# Sheet1.net
KiCad netlist of a schematic drawn in Altium Designer
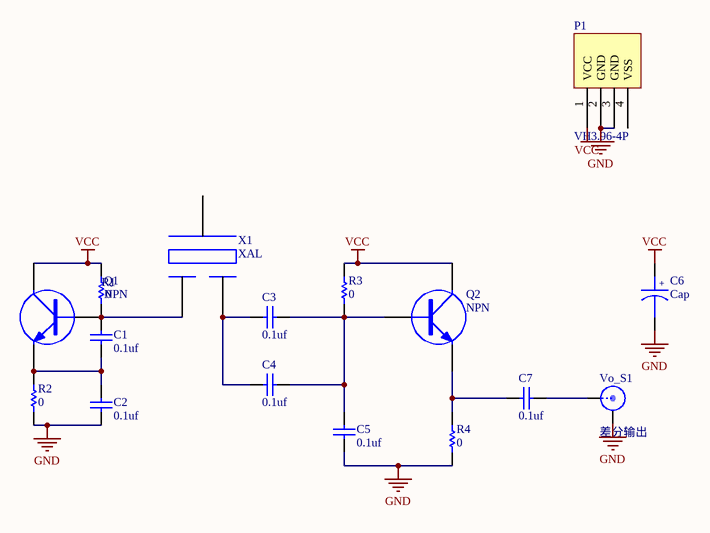
[diagram p0: Sheet1.SchDoc]

(export (version "E")
  (design (tool "Eeschema 10.0.6"))
  (components
    (comp (ref "C1") (value "0.1uf") (footprint "0805") (libsource (lib "Schlib1") (part "Cap")))
    (comp (ref "C2") (value "0.1uf") (footprint "0805") (libsource (lib "Schlib1") (part "Cap")))
    (comp (ref "C3") (value "0.1uf") (footprint "0805") (libsource (lib "Schlib1") (part "Cap")))
    (comp (ref "C4") (value "0.1uf") (footprint "0805") (libsource (lib "Schlib1") (part "Cap")))
    (comp (ref "C5") (value "0.1uf") (footprint "0805") (libsource (lib "Schlib1") (part "Cap")))
    (comp (ref "C6")
      (value "Cap")
      (footprint "7343C-TYPE_D")
      (libsource (lib "Schlib1") (part "Tantalium Cap"))
    )
    (comp (ref "C7") (value "0.1uf") (footprint "0805") (libsource (lib "Schlib1") (part "Cap")))
    (comp (ref "P1")
      (value "VH3.96-4P")
      (footprint "VH3.96-4P")
      (libsource (lib "Schlib1") (part "VH3.96-4P"))
    )
    (comp (ref "Q1")
      (value "NPN")
      (footprint "TO-92")
      (description "NPN Transistor")
      (libsource (lib "Schlib1") (part "NPN"))
    )
    (comp (ref "Q2")
      (value "NPN")
      (footprint "TO-92")
      (description "NPN Transistor")
      (libsource (lib "Schlib1") (part "NPN"))
    )
    (comp (ref "R1") (value "0") (footprint "0805") (libsource (lib "Schlib1") (part "Res")))
    (comp (ref "R2") (value "0") (footprint "0805") (libsource (lib "Schlib1") (part "Res")))
    (comp (ref "R3") (value "0") (footprint "0805") (libsource (lib "Schlib1") (part "Res")))
    (comp (ref "R4") (value "0") (footprint "0805") (libsource (lib "Schlib1") (part "Res")))
    (comp (ref "Vo_S1") (value "差分输出") (footprint "SMA-LYING") (libsource (lib "Schlib1") (part "SMA")))
    (comp (ref "X1") (value "XAL") (footprint "DIP-3P") (libsource (lib "Schlib1") (part "XAL")))
  )
  (nets
    (net (code "1") (name "GND") (class "Default")
      (node (ref "C2") (pin "1") (pinfunction "1_1") (pintype "passive"))
      (node (ref "C5") (pin "2") (pinfunction "2_2") (pintype "passive"))
      (node (ref "C6") (pin "2") (pinfunction "2_2") (pintype "passive"))
      (node (ref "P1") (pin "2") (pinfunction "GND_2") (pintype "passive"))
      (node (ref "P1") (pin "3") (pinfunction "GND_3") (pintype "passive"))
      (node (ref "R2") (pin "1") (pinfunction "1_1") (pintype "passive"))
      (node (ref "R4") (pin "1") (pinfunction "1_1") (pintype "passive"))
      (node (ref "Vo_S1") (pin "1") (pinfunction "1_1") (pintype "passive"))
    )
    (net (code "2") (name "Net-(C3-Pad2)") (class "Default")
      (node (ref "C3") (pin "2") (pinfunction "2_2") (pintype "passive"))
      (node (ref "C4") (pin "2") (pinfunction "2_2") (pintype "passive"))
      (node (ref "X1") (pin "3") (pinfunction "3_3") (pintype "passive"))
    )
    (net (code "3") (name "Net-(C7-Pad2)") (class "Default")
      (node (ref "C7") (pin "2") (pinfunction "2_2") (pintype "passive"))
      (node (ref "Vo_S1") (pin "0") (pinfunction "0_0") (pintype "passive"))
    )
    (net (code "4") (name "Net-(Q1-B)") (class "Default")
      (node (ref "C1") (pin "2") (pinfunction "2_2") (pintype "passive"))
      (node (ref "Q1") (pin "2") (pinfunction "B_2") (pintype "passive"))
      (node (ref "R1") (pin "1") (pinfunction "1_1") (pintype "passive"))
      (node (ref "X1") (pin "1") (pinfunction "1_1") (pintype "passive"))
    )
    (net (code "5") (name "Net-(Q1-E)") (class "Default")
      (node (ref "C1") (pin "1") (pinfunction "1_1") (pintype "passive"))
      (node (ref "C2") (pin "2") (pinfunction "2_2") (pintype "passive"))
      (node (ref "Q1") (pin "3") (pinfunction "E_3") (pintype "passive"))
      (node (ref "R2") (pin "2") (pinfunction "2_2") (pintype "passive"))
    )
    (net (code "6") (name "Net-(Q2-B)") (class "Default")
      (node (ref "C3") (pin "1") (pinfunction "1_1") (pintype "passive"))
      (node (ref "C4") (pin "1") (pinfunction "1_1") (pintype "passive"))
      (node (ref "C5") (pin "1") (pinfunction "1_1") (pintype "passive"))
      (node (ref "Q2") (pin "2") (pinfunction "B_2") (pintype "passive"))
      (node (ref "R3") (pin "1") (pinfunction "1_1") (pintype "passive"))
    )
    (net (code "7") (name "Net-(Q2-E)") (class "Default")
      (node (ref "C7") (pin "1") (pinfunction "1_1") (pintype "passive"))
      (node (ref "Q2") (pin "3") (pinfunction "E_3") (pintype "passive"))
      (node (ref "R4") (pin "2") (pinfunction "2_2") (pintype "passive"))
    )
    (net (code "8") (name "VCC") (class "Default")
      (node (ref "C6") (pin "1") (pinfunction "1_1") (pintype "passive"))
      (node (ref "P1") (pin "1") (pinfunction "VCC_1") (pintype "passive"))
      (node (ref "Q1") (pin "1") (pinfunction "C_1") (pintype "passive"))
      (node (ref "Q2") (pin "1") (pinfunction "C_1") (pintype "passive"))
      (node (ref "R1") (pin "2") (pinfunction "2_2") (pintype "passive"))
      (node (ref "R3") (pin "2") (pinfunction "2_2") (pintype "passive"))
    )
    (net (code "9") (name "unconnected-(P1-VSS-Pad4)") (class "Default")
      (node (ref "P1") (pin "4") (pinfunction "VSS_4") (pintype "passive"))
    )
    (net (code "10") (name "unconnected-(X1-Pad2)") (class "Default")
      (node (ref "X1") (pin "2") (pinfunction "2_2") (pintype "passive"))
    )
  )
)
